# MIXR_Power_-_Battery_Charging.net
KiCad netlist of a schematic drawn in Altium Designer
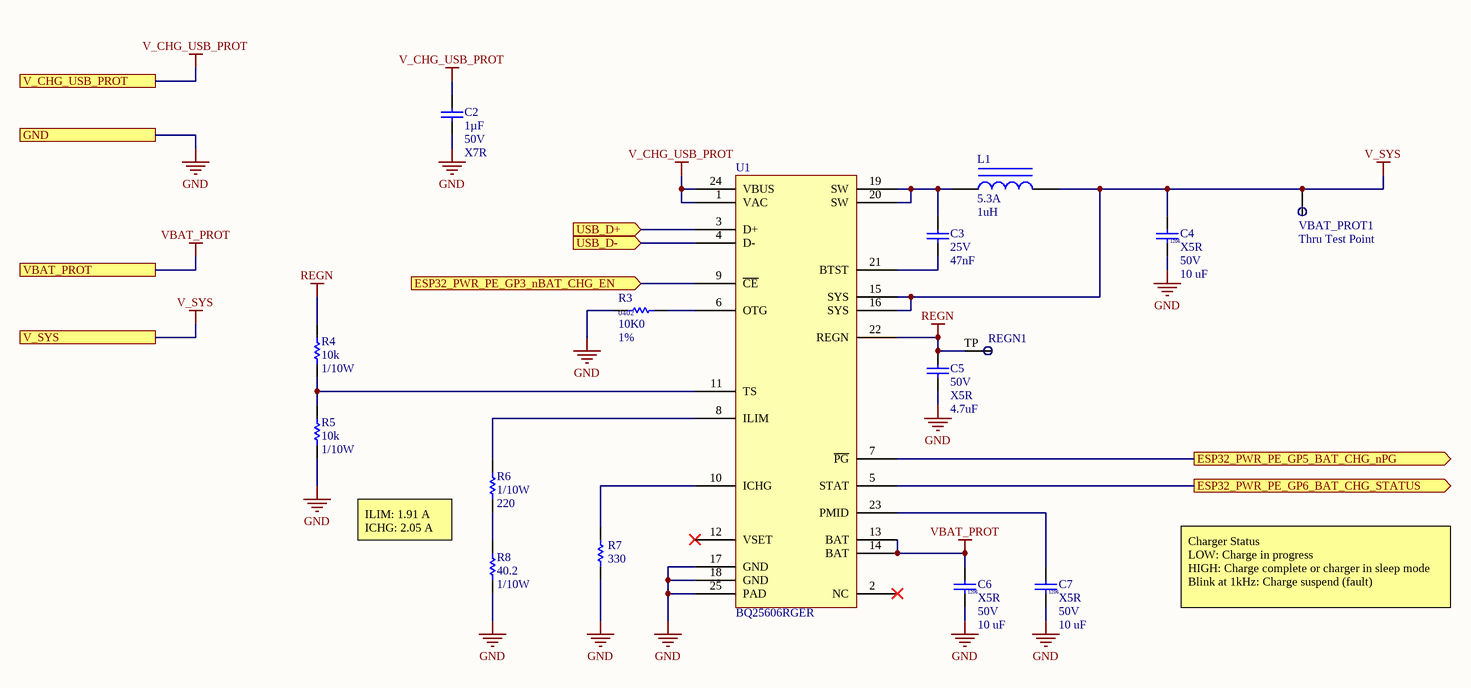
[diagram p0: MIXR Power - Battery Charging.SchDoc]

(export (version "E")
  (design (tool "Eeschema 10.0.6"))
  (components
    (comp (ref "C2")
      (value "CAP CER 1UF 50V 10% X7R 0603")
      (footprint "CAP, 0603")
      (description "1µF ±10% 50V Ceramic Capacitor X7R 0603 (1608 Metric)")
      (fields
        (field (name "TOLERANCE") "±10%")
        (field (name "CAPACITANCE") "1µF")
        (field (name "VOLTAGE") "50V")
        (field (name "TEMPERATURE COEFFICIENT") "X7R")
      )
      (libsource (lib "Schematic Diagrams") (part "CAP CER 1UF 50V 10% X7R 0603"))
    )
    (comp (ref "C3")
      (value "CAP CER 0.047UF 10% 25V X7R 0603")
      (footprint "CAP, 0603")
      (description "0.047µF ±10% 25V Ceramic Capacitor X7R 0603 (1608 Metric)")
      (fields
        (field (name "MANUFACTURER") "KEMET")
        (field (name "TOLERANCE") "10%")
        (field (name "VOLTAGE") "25V")
        (field (name "CAPACITANCE") "47nF")
      )
      (libsource (lib "Schematic Diagrams") (part "CAP CER 0.047UF 10% 25V X7R 0603"))
    )
    (comp (ref "C4")
      (value "CAP CER 10uF 50V 20% X5R 1206")
      (footprint "CAP, 1206")
      (description "10µF ±20% 50V Ceramic Capacitor X5R 1206 (3216 Metric)")
      (fields
        (field (name "MANUFACTURER") "Murata")
        (field (name "TOLERANCE") "20%")
        (field (name "RATING") "X5R")
        (field (name "VOLTAGE RATING") "50V")
        (field (name "CAPACITANCE") "10 uF")
      )
      (libsource (lib "Schematic Diagrams") (part "CAP CER 10uF 50V 20% X5R 1206"))
    )
    (comp (ref "C5")
      (value "4.7uF")
      (footprint "CAP, 0805")
      (description "4.7µF ±20% 50V Ceramic Capacitor X5R 0805 (2012 Metric)")
      (fields
        (field (name "TOLERANCE") "±20%")
        (field (name "VOLTAGE - RATED") "50V")
        (field (name "TEMPERATURE COEFFICIENT") "X5R")
        (field (name "Comment") "CAP CER 4.7UF 50V 10% X5R 0805")
      )
      (libsource (lib "Schematic Diagrams") (part "CAP CER 4.7UF 50V 10% X5R 0805"))
    )
    (comp (ref "C6")
      (value "CAP CER 10uF 50V 20% X5R 1206")
      (footprint "CAP, 1206")
      (description "10µF ±20% 50V Ceramic Capacitor X5R 1206 (3216 Metric)")
      (fields
        (field (name "MANUFACTURER") "Murata")
        (field (name "TOLERANCE") "20%")
        (field (name "RATING") "X5R")
        (field (name "VOLTAGE RATING") "50V")
        (field (name "CAPACITANCE") "10 uF")
      )
      (libsource (lib "Schematic Diagrams") (part "CAP CER 10uF 50V 20% X5R 1206"))
    )
    (comp (ref "C7")
      (value "CAP CER 10uF 50V 20% X5R 1206")
      (footprint "CAP, 1206")
      (description "10µF ±20% 50V Ceramic Capacitor X5R 1206 (3216 Metric)")
      (fields
        (field (name "MANUFACTURER") "Murata")
        (field (name "TOLERANCE") "20%")
        (field (name "RATING") "X5R")
        (field (name "VOLTAGE RATING") "50V")
        (field (name "CAPACITANCE") "10 uF")
      )
      (libsource (lib "Schematic Diagrams") (part "CAP CER 10uF 50V 20% X5R 1206"))
    )
    (comp (ref "L1")
      (value "IND 1UH 5.3A 20 MOHM SMD")
      (footprint "IND 1UH 5.3A 20 MOHM 5020")
      (fields
        (field (name "MANUFACTURER") "Wurth Electronics")
        (field (name "MANUFACTURER PART NUMBER") "74437334010")
        (field (name "TOLERANCE") "20%")
        (field (name "CURRENT RATING") "5.3A")
        (field (name "INDUCTANCE") "1uH")
      )
      (libsource (lib "Schematic Diagrams") (part "IND 1UH 5.3A 20 MOHM SMD"))
    )
    (comp (ref "R3")
      (value "RES 10K OHM 1% 1/16W 0402")
      (footprint "RES 0402")
      (description "Surface Mount Thick Film Resistor, Rc Series, 10 Kohm, 62.5 Mw, - 1%, 50 V, 0402 [1005 Metric]")
      (fields
        (field (name "MANUFACTURER") "Yageo")
        (field (name "MANUFACTURER PART NUMBER") "RC0402FR-0710KL")
        (field (name "RESISTANCE") "10K0")
        (field (name "TOLERANCE") "1%")
      )
      (libsource (lib "Schematic Diagrams") (part "RES 10K OHM 1% 1/16W 0402"))
    )
    (comp (ref "R4")
      (value "RES 10K OHM 1% 1/10W 0603")
      (footprint "RES, 0603")
      (description "RES SMD 10K OHM 1% 1/10W 0603")
      (fields
        (field (name "TOLERANCE") "±1%")
        (field (name "RESISTANCE") "10k")
        (field (name "POWER") "1/10W")
      )
      (libsource (lib "Schematic Diagrams") (part "RES 10K OHM 1% 1/10W 0603"))
    )
    (comp (ref "R5")
      (value "RES 10K OHM 1% 1/10W 0603")
      (footprint "RES, 0603")
      (description "RES SMD 10K OHM 1% 1/10W 0603")
      (fields
        (field (name "TOLERANCE") "±1%")
        (field (name "RESISTANCE") "10k")
        (field (name "POWER") "1/10W")
      )
      (libsource (lib "Schematic Diagrams") (part "RES 10K OHM 1% 1/10W 0603"))
    )
    (comp (ref "R6")
      (value "RES 220 OHM 1% 1/10W 0603")
      (footprint "RES, 0603")
      (description "220 Ohms ±1% 0.1W, 1/10W Chip Resistor 0603 (1608 Metric) Moisture Resistant Thick Film")
      (fields
        (field (name "MANUFACTURER") "Yageo")
        (field (name "MANUFACTURER PART NUMBER") "RC0603FR-07220RL")
        (field (name "POWER (WATTS)") "1/10W")
        (field (name "RESISTANCE") "220")
      )
      (libsource (lib "Schematic Diagrams") (part "RES 220 OHM 1% 1/10W 0603"))
    )
    (comp (ref "R7")
      (value "330")
      (footprint "RES, 0603")
      (fields
        (field (name "MANUFACTURER") "TE Connectivity")
        (field (name "MANUFACTURER PART NUMBER") "CRGCQ0603F330R")
        (field (name "Comment") "RES 330 OHM 1% 1/10W 0603")
      )
      (libsource (lib "Schematic Diagrams") (part "RES 330 OHM 1% 1/10W 0603"))
    )
    (comp (ref "R8")
      (value "RES 40.2 OHM 0.5% 1/10W 0603")
      (footprint "RES, 0603")
      (description "RES SMD 40.2 OHM 0.5% 1/10W 0603")
      (fields
        (field (name "TOLERANCE") "±0.5%")
        (field (name "RESISTANCE") "40.2")
        (field (name "POWER") "1/10W")
      )
      (libsource (lib "Schematic Diagrams") (part "RES 40.2 OHM 0.5% 1/10W 0603"))
    )
    (comp (ref "REGN1")
      (value "Test Point")
      (footprint "Test Point")
      (libsource (lib "Schematic Diagrams") (part "Test Point"))
    )
    (comp (ref "U1")
      (value "IC BATT CHG LI-ION 1 CELL 24-VQFN")
      (footprint "IC BATT CHG LI-ION 1 CELL 24-VQFN")
      (description "Charger IC Lithium Ion/Polymer 24-VQFN (4x4)")
      (fields
        (field (name "MANUFACTURER") "Texas Instruments")
        (field (name "MANUFACTURER PART NUMBER") "BQ25606RGER")
      )
      (libsource (lib "Schematic Diagrams") (part "IC BATT CHG LI-ION 1 CELL 24-VQFN"))
    )
    (comp (ref "VBAT_PROT1")
      (value "Thru Test Point")
      (footprint "Thru Test Point")
      (libsource (lib "Schematic Diagrams") (part "Thru Test Point"))
    )
  )
  (nets
    (net (code "1") (name "/ESP32_PWR_PE_GP3_nBAT_CHG_EN") (class "Default")
      (node (ref "U1") (pin "9") (pinfunction "~{CE}_9") (pintype "passive"))
    )
    (net (code "2") (name "/ESP32_PWR_PE_GP5_BAT_CHG_nPG") (class "Default")
      (node (ref "U1") (pin "7") (pinfunction "~{PG}_7") (pintype "passive"))
    )
    (net (code "3") (name "/ESP32_PWR_PE_GP6_BAT_CHG_STATUS") (class "Default")
      (node (ref "U1") (pin "5") (pinfunction "STAT_5") (pintype "passive"))
    )
    (net (code "4") (name "/USB_D+") (class "Default")
      (node (ref "U1") (pin "3") (pinfunction "D+_3") (pintype "passive"))
    )
    (net (code "5") (name "/USB_D-") (class "Default")
      (node (ref "U1") (pin "4") (pinfunction "D-_4") (pintype "passive"))
    )
    (net (code "6") (name "GND") (class "Default")
      (node (ref "C2") (pin "2") (pinfunction "2_2") (pintype "passive"))
      (node (ref "C4") (pin "2") (pinfunction "2_2") (pintype "passive"))
      (node (ref "C5") (pin "2") (pinfunction "2_2") (pintype "passive"))
      (node (ref "C6") (pin "2") (pinfunction "2_2") (pintype "passive"))
      (node (ref "C7") (pin "2") (pinfunction "2_2") (pintype "passive"))
      (node (ref "R3") (pin "1") (pinfunction "1_1") (pintype "passive"))
      (node (ref "R5") (pin "2") (pinfunction "2_2") (pintype "passive"))
      (node (ref "R7") (pin "2") (pinfunction "2_2") (pintype "passive"))
      (node (ref "R8") (pin "2") (pinfunction "2_2") (pintype "passive"))
      (node (ref "U1") (pin "17") (pinfunction "GND_17") (pintype "passive"))
      (node (ref "U1") (pin "18") (pinfunction "GND_18") (pintype "passive"))
      (node (ref "U1") (pin "25") (pinfunction "PAD_25") (pintype "passive"))
    )
    (net (code "7") (name "Net-(C3-Pad1)") (class "Default")
      (node (ref "C3") (pin "1") (pinfunction "1_1") (pintype "passive"))
      (node (ref "L1") (pin "1") (pinfunction "1_1") (pintype "passive"))
      (node (ref "U1") (pin "19") (pinfunction "SW_19") (pintype "passive"))
      (node (ref "U1") (pin "20") (pinfunction "SW_20") (pintype "passive"))
    )
    (net (code "8") (name "Net-(R6-Pad2)") (class "Default")
      (node (ref "R6") (pin "2") (pinfunction "2_2") (pintype "passive"))
      (node (ref "R8") (pin "1") (pinfunction "1_1") (pintype "passive"))
    )
    (net (code "9") (name "Net-(U1-BTST)") (class "Default")
      (node (ref "C3") (pin "2") (pinfunction "2_2") (pintype "passive"))
      (node (ref "U1") (pin "21") (pinfunction "BTST_21") (pintype "passive"))
    )
    (net (code "10") (name "Net-(U1-ICHG)") (class "Default")
      (node (ref "R7") (pin "1") (pinfunction "1_1") (pintype "passive"))
      (node (ref "U1") (pin "10") (pinfunction "ICHG_10") (pintype "passive"))
    )
    (net (code "11") (name "Net-(U1-ILIM)") (class "Default")
      (node (ref "R6") (pin "1") (pinfunction "1_1") (pintype "passive"))
      (node (ref "U1") (pin "8") (pinfunction "ILIM_8") (pintype "passive"))
    )
    (net (code "12") (name "Net-(U1-OTG)") (class "Default")
      (node (ref "R3") (pin "2") (pinfunction "2_2") (pintype "passive"))
      (node (ref "U1") (pin "6") (pinfunction "OTG_6") (pintype "passive"))
    )
    (net (code "13") (name "Net-(U1-PMID)") (class "Default")
      (node (ref "C7") (pin "1") (pinfunction "1_1") (pintype "passive"))
      (node (ref "U1") (pin "23") (pinfunction "PMID_23") (pintype "passive"))
    )
    (net (code "14") (name "Net-(U1-TS)") (class "Default")
      (node (ref "R4") (pin "2") (pinfunction "2_2") (pintype "passive"))
      (node (ref "R5") (pin "1") (pinfunction "1_1") (pintype "passive"))
      (node (ref "U1") (pin "11") (pinfunction "TS_11") (pintype "passive"))
    )
    (net (code "15") (name "REGN") (class "Default")
      (node (ref "C5") (pin "1") (pinfunction "1_1") (pintype "passive"))
      (node (ref "R4") (pin "1") (pinfunction "1_1") (pintype "passive"))
      (node (ref "REGN1") (pin "TP") (pinfunction "1_TP") (pintype "passive"))
      (node (ref "U1") (pin "22") (pinfunction "REGN_22") (pintype "passive"))
    )
    (net (code "16") (name "VBAT_PROT") (class "Default")
      (node (ref "C6") (pin "1") (pinfunction "1_1") (pintype "passive"))
      (node (ref "U1") (pin "13") (pinfunction "BAT_13") (pintype "passive"))
      (node (ref "U1") (pin "14") (pinfunction "BAT_14") (pintype "passive"))
    )
    (net (code "17") (name "V_CHG_USB_PROT") (class "Default")
      (node (ref "C2") (pin "1") (pinfunction "1_1") (pintype "passive"))
      (node (ref "U1") (pin "1") (pinfunction "VAC_1") (pintype "passive"))
      (node (ref "U1") (pin "24") (pinfunction "VBUS_24") (pintype "passive"))
    )
    (net (code "18") (name "V_SYS") (class "Default")
      (node (ref "C4") (pin "1") (pinfunction "1_1") (pintype "passive"))
      (node (ref "L1") (pin "2") (pinfunction "2_2") (pintype "passive"))
      (node (ref "U1") (pin "15") (pinfunction "SYS_15") (pintype "passive"))
      (node (ref "U1") (pin "16") (pinfunction "SYS_16") (pintype "passive"))
      (node (ref "VBAT_PROT1") (pin "TH_TP") (pinfunction "1_TH_TP") (pintype "passive"))
    )
    (net (code "19") (name "unconnected-(U1-NC-Pad2)") (class "Default")
      (node (ref "U1") (pin "2") (pinfunction "NC_2") (pintype "passive+no_connect"))
    )
    (net (code "20") (name "unconnected-(U1-VSET-Pad12)") (class "Default")
      (node (ref "U1") (pin "12") (pinfunction "VSET_12") (pintype "passive+no_connect"))
    )
  )
)
